# PDB2_1.net
KiCad netlist of a schematic drawn in EAGLE
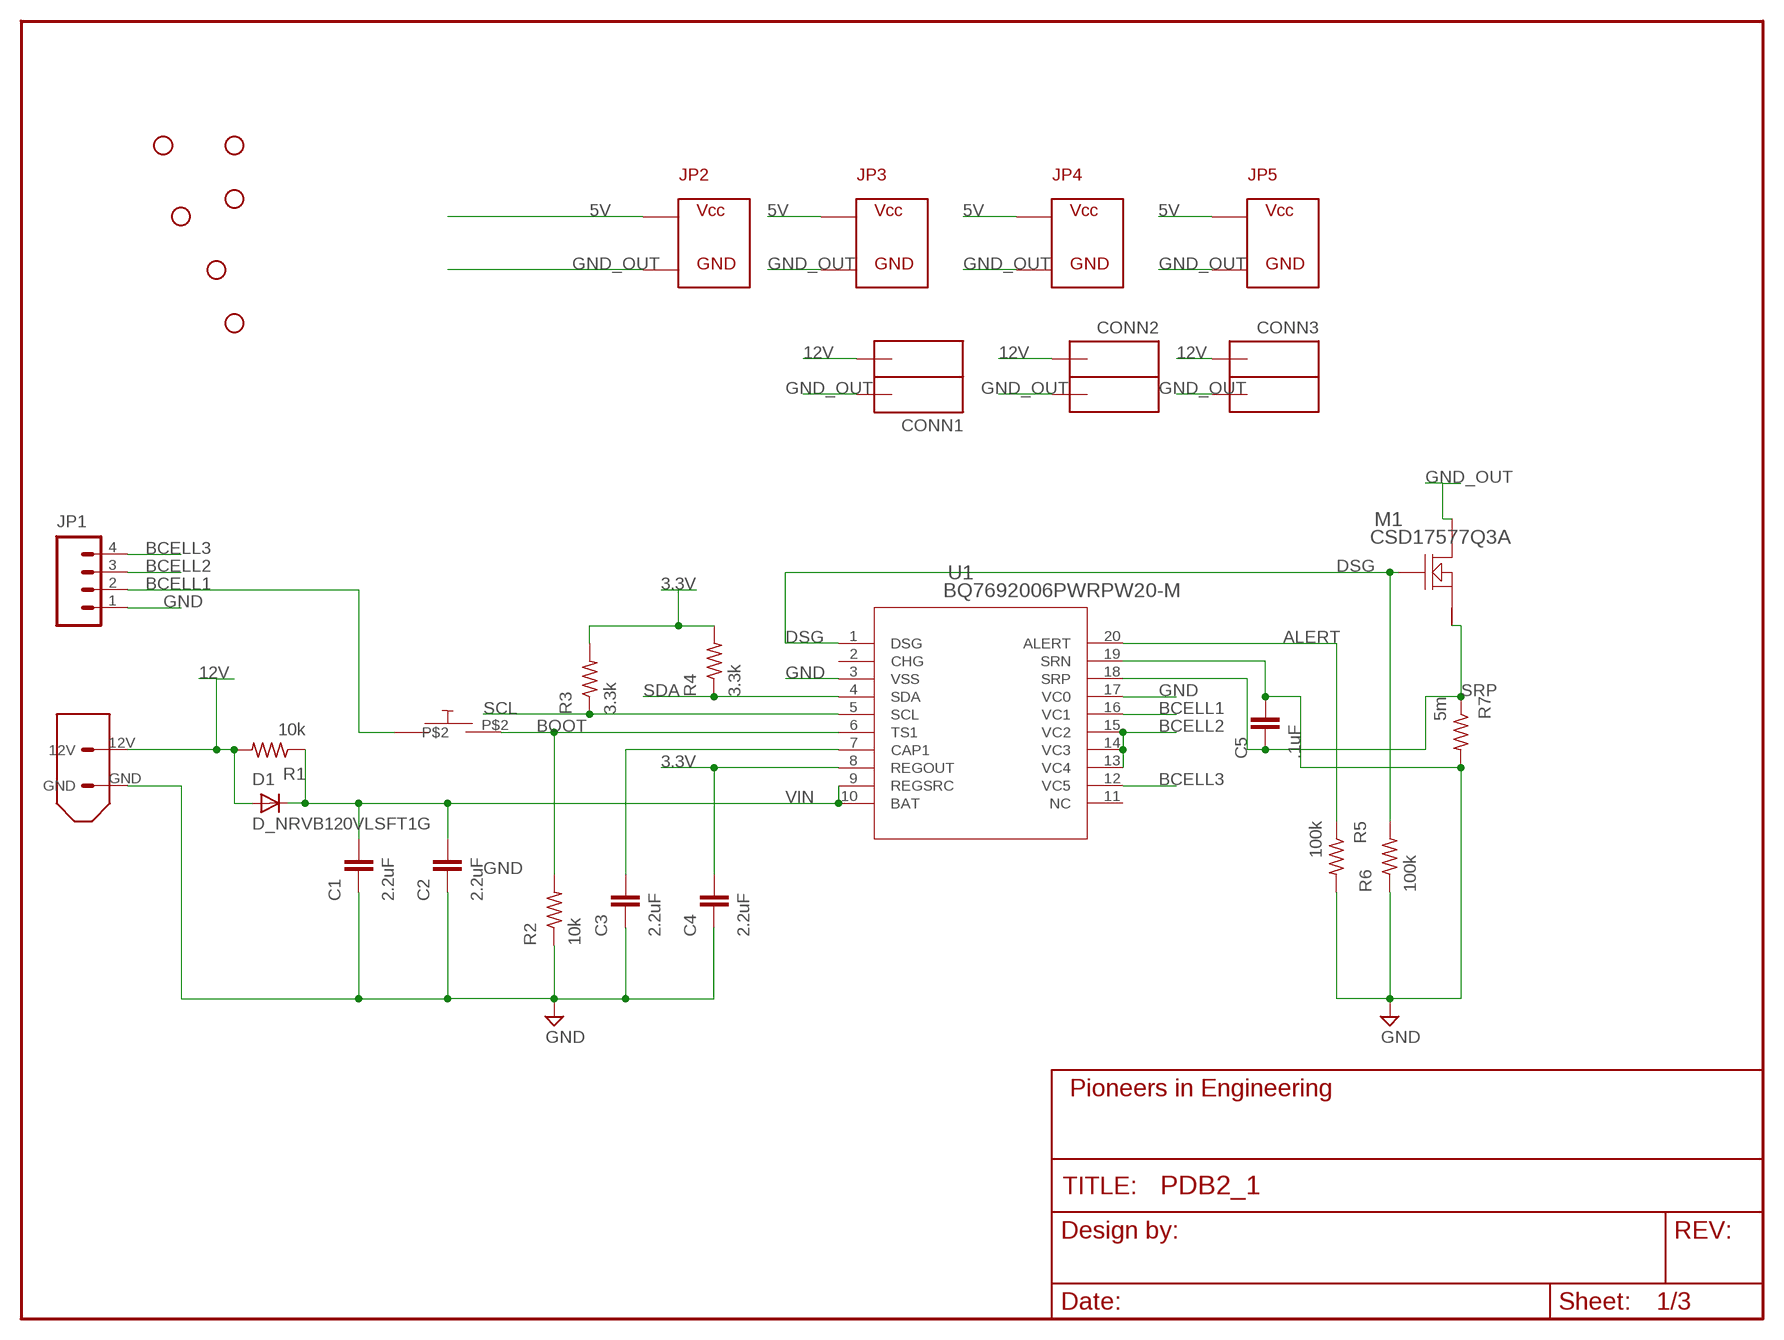
[diagram p0: schematic, sheet 1]
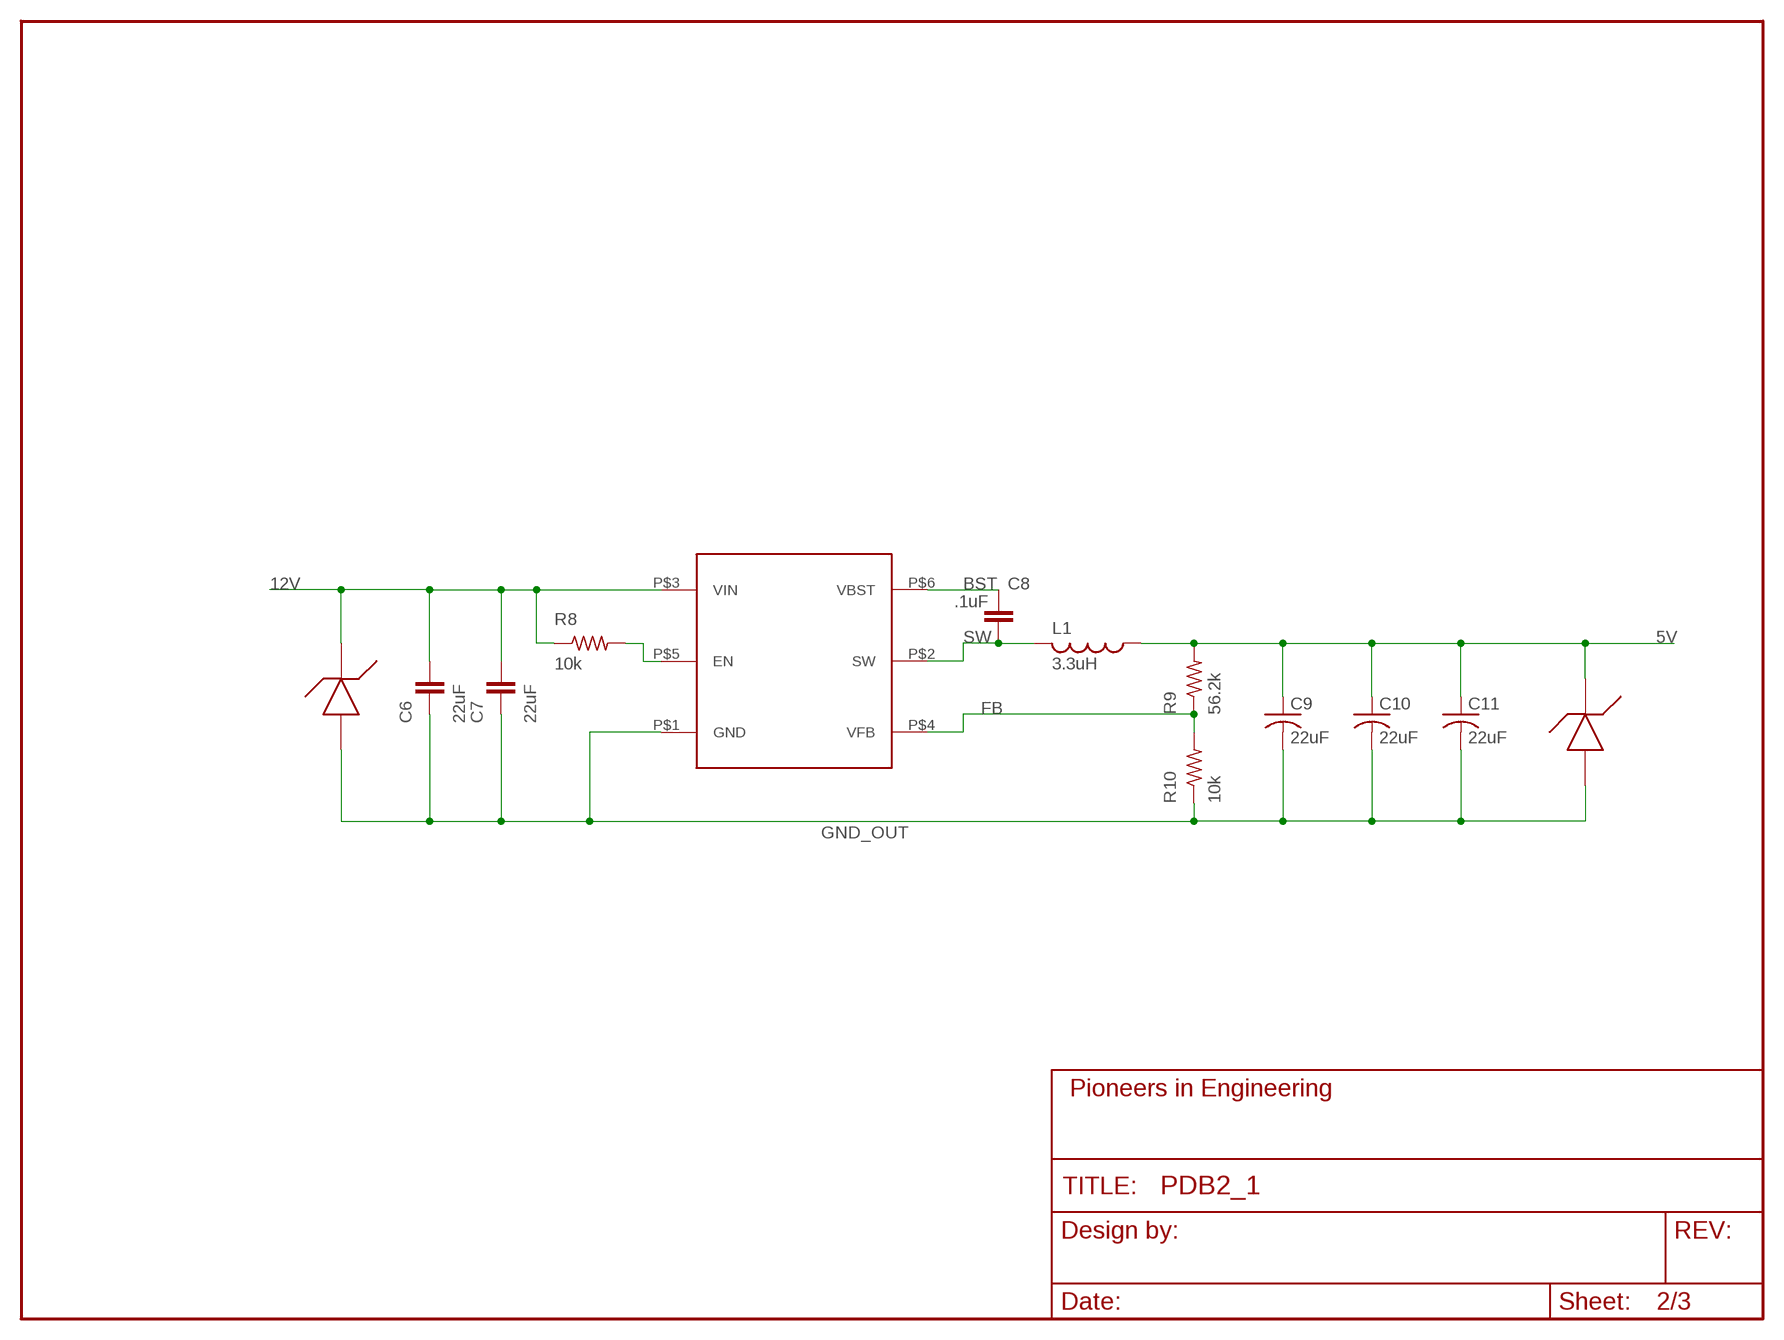
[diagram p1: schematic, sheet 2]
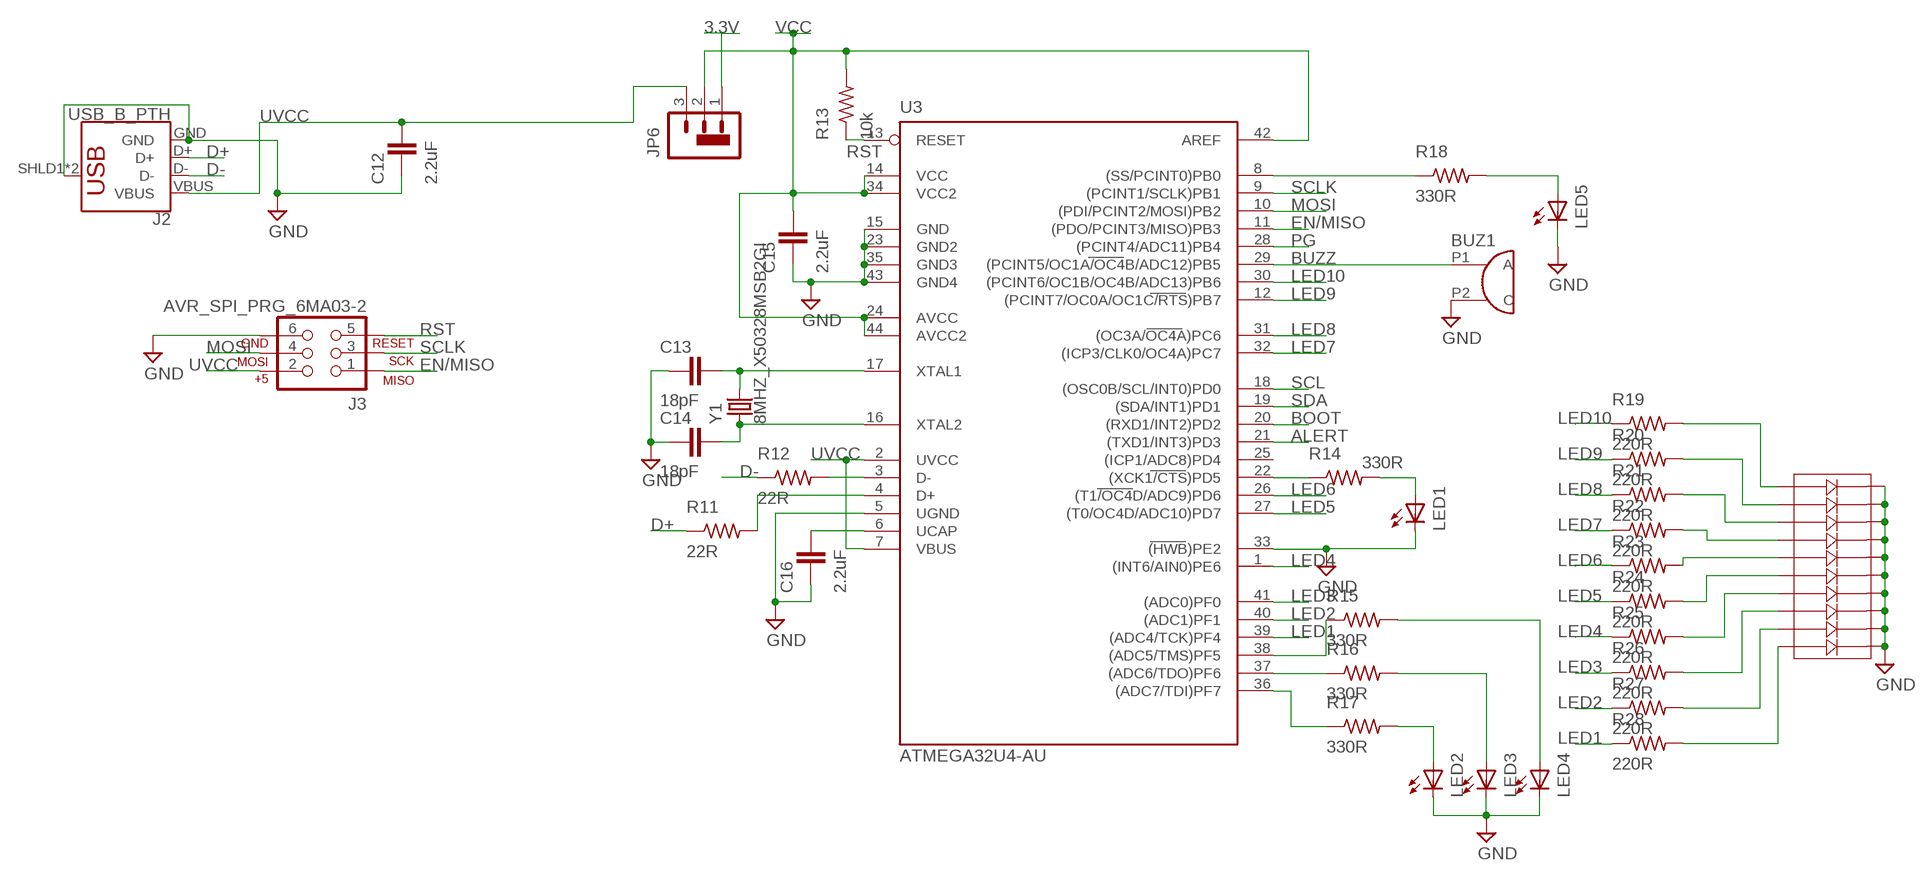
[diagram p2: schematic, sheet 3]

(export (version "E")
  (design (tool "Eeschema 10.0.6"))
  (components
    (comp (ref "BUZ1")
      (value "BUZZER3.3VBUZZER")
      (footprint "eagle-import:BUZZER_3.3V")
      (libsource (lib "eagle-import") (part "BUZZER3.3VBUZZER"))
    )
    (comp (ref "C12")
      (value "2.2uF")
      (footprint "eagle-import:0603-CAP")
      (libsource (lib "eagle-import") (part "CAP0603-CAP"))
    )
    (comp (ref "C13")
      (value "18pF")
      (footprint "eagle-import:0603-CAP")
      (libsource (lib "eagle-import") (part "CAP0603-CAP"))
    )
    (comp (ref "C14")
      (value "18pF")
      (footprint "eagle-import:0603-CAP")
      (libsource (lib "eagle-import") (part "CAP0603-CAP"))
    )
    (comp (ref "C15")
      (value "2.2uF")
      (footprint "eagle-import:0603-CAP")
      (libsource (lib "eagle-import") (part "CAP0603-CAP"))
    )
    (comp (ref "C16")
      (value "2.2uF")
      (footprint "eagle-import:0603-CAP")
      (libsource (lib "eagle-import") (part "CAP0603-CAP"))
    )
    (comp (ref "J2")
      (value "USB_B_PTH")
      (footprint "eagle-import:USB-B-PTH")
      (libsource (lib "eagle-import") (part "USB_B_PTH"))
    )
    (comp (ref "J3")
      (value "AVR_SPI_PRG_6MA03-2")
      (footprint "eagle-import:MA03-2")
      (libsource (lib "eagle-import") (part "AVR_SPI_PRG_6MA03-2"))
    )
    (comp (ref "JP6")
      (value "JMP-OPTION")
      (footprint "eagle-import:1X03-JMP-OPTION")
      (libsource (lib "eagle-import") (part "JMP-OPTION"))
    )
    (comp (ref "LED1")
      (value "LED0805")
      (footprint "eagle-import:LED-0805")
      (libsource (lib "eagle-import") (part "LED0805"))
    )
    (comp (ref "LED2")
      (value "LED0805")
      (footprint "eagle-import:LED-0805")
      (libsource (lib "eagle-import") (part "LED0805"))
    )
    (comp (ref "LED3")
      (value "LED0805")
      (footprint "eagle-import:LED-0805")
      (libsource (lib "eagle-import") (part "LED0805"))
    )
    (comp (ref "LED4")
      (value "LED0805")
      (footprint "eagle-import:LED-0805")
      (libsource (lib "eagle-import") (part "LED0805"))
    )
    (comp (ref "LED5")
      (value "LED0805")
      (footprint "eagle-import:LED-0805")
      (libsource (lib "eagle-import") (part "LED0805"))
    )
    (comp (ref "LED6")
      (value "BAR_SEGMENT_DISPLAY")
      (footprint "eagle-import:BAR_SEGMENT_DISPLAY")
      (libsource (lib "eagle-import") (part "BAR_SEGMENT_DISPLAY"))
    )
    (comp (ref "R11")
      (value "22R")
      (footprint "eagle-import:R0603")
      (fields (field (name "MANUFACTURER") "Rohm Semiconductor"))
      (libsource (lib "eagle-import") (part "R-US_R0603"))
    )
    (comp (ref "R12")
      (value "22R")
      (footprint "eagle-import:R0603")
      (fields (field (name "MANUFACTURER") "Rohm Semiconductor"))
      (libsource (lib "eagle-import") (part "R-US_R0603"))
    )
    (comp (ref "R13")
      (value "10k")
      (footprint "eagle-import:R0603")
      (fields (field (name "MANUFACTURER") "Rohm Semiconductor"))
      (libsource (lib "eagle-import") (part "R-US_R0603"))
    )
    (comp (ref "R14")
      (value "330R")
      (footprint "eagle-import:R0603")
      (fields (field (name "MANUFACTURER") "Rohm Semiconductor"))
      (libsource (lib "eagle-import") (part "R-US_R0603"))
    )
    (comp (ref "R15")
      (value "330R")
      (footprint "eagle-import:R0603")
      (fields (field (name "MANUFACTURER") "Rohm Semiconductor"))
      (libsource (lib "eagle-import") (part "R-US_R0603"))
    )
    (comp (ref "R16")
      (value "330R")
      (footprint "eagle-import:R0603")
      (fields (field (name "MANUFACTURER") "Rohm Semiconductor"))
      (libsource (lib "eagle-import") (part "R-US_R0603"))
    )
    (comp (ref "R17")
      (value "330R")
      (footprint "eagle-import:R0603")
      (fields (field (name "MANUFACTURER") "Rohm Semiconductor"))
      (libsource (lib "eagle-import") (part "R-US_R0603"))
    )
    (comp (ref "R18")
      (value "330R")
      (footprint "eagle-import:R0603")
      (fields (field (name "MANUFACTURER") "Rohm Semiconductor"))
      (libsource (lib "eagle-import") (part "R-US_R0603"))
    )
    (comp (ref "R19")
      (value "220R")
      (footprint "eagle-import:R0603")
      (fields (field (name "MANUFACTURER") "Rohm Semiconductor"))
      (libsource (lib "eagle-import") (part "R-US_R0603"))
    )
    (comp (ref "R20")
      (value "220R")
      (footprint "eagle-import:R0603")
      (fields (field (name "MANUFACTURER") "Rohm Semiconductor"))
      (libsource (lib "eagle-import") (part "R-US_R0603"))
    )
    (comp (ref "R21")
      (value "220R")
      (footprint "eagle-import:R0603")
      (fields (field (name "MANUFACTURER") "Rohm Semiconductor"))
      (libsource (lib "eagle-import") (part "R-US_R0603"))
    )
    (comp (ref "R22")
      (value "220R")
      (footprint "eagle-import:R0603")
      (fields (field (name "MANUFACTURER") "Rohm Semiconductor"))
      (libsource (lib "eagle-import") (part "R-US_R0603"))
    )
    (comp (ref "R23")
      (value "220R")
      (footprint "eagle-import:R0603")
      (fields (field (name "MANUFACTURER") "Rohm Semiconductor"))
      (libsource (lib "eagle-import") (part "R-US_R0603"))
    )
    (comp (ref "R24")
      (value "220R")
      (footprint "eagle-import:R0603")
      (fields (field (name "MANUFACTURER") "Rohm Semiconductor"))
      (libsource (lib "eagle-import") (part "R-US_R0603"))
    )
    (comp (ref "R25")
      (value "220R")
      (footprint "eagle-import:R0603")
      (fields (field (name "MANUFACTURER") "Rohm Semiconductor"))
      (libsource (lib "eagle-import") (part "R-US_R0603"))
    )
    (comp (ref "R26")
      (value "220R")
      (footprint "eagle-import:R0603")
      (fields (field (name "MANUFACTURER") "Rohm Semiconductor"))
      (libsource (lib "eagle-import") (part "R-US_R0603"))
    )
    (comp (ref "R27")
      (value "220R")
      (footprint "eagle-import:R0603")
      (fields (field (name "MANUFACTURER") "Rohm Semiconductor"))
      (libsource (lib "eagle-import") (part "R-US_R0603"))
    )
    (comp (ref "R28")
      (value "220R")
      (footprint "eagle-import:R0603")
      (fields (field (name "MANUFACTURER") "Rohm Semiconductor"))
      (libsource (lib "eagle-import") (part "R-US_R0603"))
    )
    (comp (ref "U3")
      (value "ATMEGA32U4-AU")
      (footprint "eagle-import:TQFP44")
      (libsource (lib "eagle-import") (part "ATMEGA32U4-AU"))
    )
    (comp (ref "Y1")
      (value "8MHZ_X50328MSB2GI")
      (footprint "eagle-import:SMD-5032_2P")
      (libsource (lib "eagle-import") (part "8MHZ_X50328MSB2GI"))
    )
    (comp (ref "C6")
      (value "22uF")
      (footprint "eagle-import:0805")
      (libsource (lib "eagle-import") (part "CAP0805"))
    )
    (comp (ref "C7")
      (value "22uF")
      (footprint "eagle-import:0805")
      (libsource (lib "eagle-import") (part "CAP0805"))
    )
    (comp (ref "C8")
      (value ".1uF")
      (footprint "eagle-import:0603-CAP")
      (libsource (lib "eagle-import") (part "CAP0603-CAP"))
    )
    (comp (ref "C9")
      (value "22uF")
      (footprint "eagle-import:C0805")
      (libsource (lib "eagle-import") (part "C-USC0805"))
    )
    (comp (ref "C10")
      (value "22uF")
      (footprint "eagle-import:C0805")
      (libsource (lib "eagle-import") (part "C-USC0805"))
    )
    (comp (ref "C11")
      (value "22uF")
      (footprint "eagle-import:C0805")
      (libsource (lib "eagle-import") (part "C-USC0805"))
    )
    (comp (ref "D2")
      (value "BZT52C2VXX_ZENER")
      (footprint "eagle-import:SOD-123")
      (libsource (lib "eagle-import") (part "BZT52C2VXX_ZENER"))
    )
    (comp (ref "D3")
      (value "BZT52C2VXX_ZENER")
      (footprint "eagle-import:SOD-123")
      (libsource (lib "eagle-import") (part "BZT52C2VXX_ZENER"))
    )
    (comp (ref "L1")
      (value "3.3uH")
      (footprint "eagle-import:MWSA0402S")
      (libsource (lib "eagle-import") (part "MWSA0420S_INDUCTORMW"))
    )
    (comp (ref "R8")
      (value "10k")
      (footprint "eagle-import:R0603")
      (fields (field (name "MANUFACTURER") "Rohm Semiconductor"))
      (libsource (lib "eagle-import") (part "R-US_R0603"))
    )
    (comp (ref "R9")
      (value "56.2k")
      (footprint "eagle-import:R0603")
      (fields (field (name "MANUFACTURER") "Rohm Semiconductor"))
      (libsource (lib "eagle-import") (part "R-US_R0603"))
    )
    (comp (ref "R10")
      (value "10k")
      (footprint "eagle-import:R0603")
      (fields (field (name "MANUFACTURER") "Rohm Semiconductor"))
      (libsource (lib "eagle-import") (part "R-US_R0603"))
    )
    (comp (ref "U2")
      (value "TPS563200")
      (footprint "eagle-import:SOT-23_6PIN_COPY")
      (libsource (lib "eagle-import") (part "TPS563200"))
    )
    (comp (ref "C1")
      (value "2.2uF")
      (footprint "eagle-import:0603-CAP")
      (libsource (lib "eagle-import") (part "CAP0603-CAP"))
    )
    (comp (ref "C2")
      (value "2.2uF")
      (footprint "eagle-import:0603-CAP")
      (libsource (lib "eagle-import") (part "CAP0603-CAP"))
    )
    (comp (ref "C3")
      (value "2.2uF")
      (footprint "eagle-import:0603-CAP")
      (libsource (lib "eagle-import") (part "CAP0603-CAP"))
    )
    (comp (ref "C4")
      (value "2.2uF")
      (footprint "eagle-import:0603-CAP")
      (libsource (lib "eagle-import") (part "CAP0603-CAP"))
    )
    (comp (ref "C5")
      (value ".1uF")
      (footprint "eagle-import:0603-CAP")
      (libsource (lib "eagle-import") (part "CAP0603-CAP"))
    )
    (comp (ref "CONN1")
      (value "ANDERSONVERTICAL")
      (footprint "eagle-import:ANDERSON_VERTICAL")
      (libsource (lib "eagle-import") (part "ANDERSONVERTICAL"))
    )
    (comp (ref "CONN2")
      (value "ANDERSONVERTICAL")
      (footprint "eagle-import:ANDERSON_VERTICAL")
      (libsource (lib "eagle-import") (part "ANDERSONVERTICAL"))
    )
    (comp (ref "CONN3")
      (value "ANDERSONVERTICAL")
      (footprint "eagle-import:ANDERSON_VERTICAL")
      (libsource (lib "eagle-import") (part "ANDERSONVERTICAL"))
    )
    (comp (ref "D1")
      (value "D_NRVB120VLSFT1G")
      (footprint "eagle-import:ON_SEMI_SOD-123F")
      (libsource (lib "eagle-import") (part "D_NRVB120VLSFT1G"))
    )
    (comp (ref "J1")
      (value "XT60CONNECTOR")
      (footprint "eagle-import:XT60CONNECTOR")
      (fields (field (name "PARTNUMBER") "PRT-10474 "))
      (libsource (lib "eagle-import") (part "XT60CONNECTOR"))
    )
    (comp (ref "JP1")
      (value "M041X04-MTA")
      (footprint "eagle-import:1X04-MTA")
      (libsource (lib "eagle-import") (part "M041X04-MTA"))
    )
    (comp (ref "JP2")
      (value "ATX")
      (footprint "eagle-import:ATX")
      (libsource (lib "eagle-import") (part "ATX"))
    )
    (comp (ref "JP3")
      (value "ATX")
      (footprint "eagle-import:ATX")
      (libsource (lib "eagle-import") (part "ATX"))
    )
    (comp (ref "JP4")
      (value "ATX")
      (footprint "eagle-import:ATX")
      (libsource (lib "eagle-import") (part "ATX"))
    )
    (comp (ref "JP5")
      (value "ATX")
      (footprint "eagle-import:ATX")
      (libsource (lib "eagle-import") (part "ATX"))
    )
    (comp (ref "M1")
      (value "CSD17577Q3A")
      (footprint "eagle-import:DNH0008A")
      (fields
        (field (name "MANUFACTURER_PART_NUMBER") "CSD17579Q3A")
        (field (name "MANUFACTURER_PART_NUMBER_1") "CSD17577Q3A")
      )
      (libsource (lib "eagle-import") (part "NMOS_CSD17579Q3A"))
    )
    (comp (ref "R1")
      (value "10k")
      (footprint "eagle-import:R0603")
      (fields (field (name "MANUFACTURER") "Rohm Semiconductor"))
      (libsource (lib "eagle-import") (part "R-US_R0603"))
    )
    (comp (ref "R2")
      (value "10k")
      (footprint "eagle-import:R0603")
      (fields (field (name "MANUFACTURER") "Rohm Semiconductor"))
      (libsource (lib "eagle-import") (part "R-US_R0603"))
    )
    (comp (ref "R3")
      (value "3.3k")
      (footprint "eagle-import:R0603")
      (fields (field (name "MANUFACTURER") "Rohm Semiconductor"))
      (libsource (lib "eagle-import") (part "R-US_R0603"))
    )
    (comp (ref "R4")
      (value "3.3k")
      (footprint "eagle-import:R0603")
      (fields (field (name "MANUFACTURER") "Rohm Semiconductor"))
      (libsource (lib "eagle-import") (part "R-US_R0603"))
    )
    (comp (ref "R5")
      (value "100k")
      (footprint "eagle-import:R0603")
      (fields (field (name "MANUFACTURER") "Rohm Semiconductor"))
      (libsource (lib "eagle-import") (part "R-US_R0603"))
    )
    (comp (ref "R6")
      (value "100k")
      (footprint "eagle-import:R0603")
      (fields (field (name "MANUFACTURER") "Rohm Semiconductor"))
      (libsource (lib "eagle-import") (part "R-US_R0603"))
    )
    (comp (ref "R7")
      (value "5m")
      (footprint "eagle-import:R2512")
      (libsource (lib "eagle-import") (part "R-US_R2512"))
    )
    (comp (ref "STANDOFF1")
      (value "STAND-OFFTIGHT")
      (footprint "eagle-import:STAND-OFF-TIGHT")
      (libsource (lib "eagle-import") (part "STAND-OFFTIGHT"))
    )
    (comp (ref "STANDOFF2")
      (value "STAND-OFFTIGHT")
      (footprint "eagle-import:STAND-OFF-TIGHT")
      (libsource (lib "eagle-import") (part "STAND-OFFTIGHT"))
    )
    (comp (ref "STANDOFF3")
      (value "STAND-OFFTIGHT")
      (footprint "eagle-import:STAND-OFF-TIGHT")
      (libsource (lib "eagle-import") (part "STAND-OFFTIGHT"))
    )
    (comp (ref "STANDOFF4")
      (value "STAND-OFFTIGHT")
      (footprint "eagle-import:STAND-OFF-TIGHT")
      (libsource (lib "eagle-import") (part "STAND-OFFTIGHT"))
    )
    (comp (ref "STANDOFF5")
      (value "STAND-OFFTIGHT")
      (footprint "eagle-import:STAND-OFF-TIGHT")
      (libsource (lib "eagle-import") (part "STAND-OFFTIGHT"))
    )
    (comp (ref "STANDOFF6")
      (value "STAND-OFFTIGHT")
      (footprint "eagle-import:STAND-OFF-TIGHT")
      (libsource (lib "eagle-import") (part "STAND-OFFTIGHT"))
    )
    (comp (ref "SW1")
      (value "PUSH_BUTTON")
      (footprint "eagle-import:BUTTON_K12A")
      (libsource (lib "eagle-import") (part "PUSH_BUTTON"))
    )
    (comp (ref "U1")
      (value "BQ7692006PWRPW20-M")
      (footprint "eagle-import:PW20-M")
      (fields (field (name "MANUFACTURER_PART_NUMBER") "BQ7692006PWR"))
      (libsource (lib "eagle-import") (part "BQ7692006PWRPW20-M"))
    )
  )
  (nets
    (net (code "1") (name "3.3V") (class "Default")
      (node (ref "C4") (pin "2") (pinfunction "2_2") (pintype "passive"))
      (node (ref "JP6") (pin "1") (pinfunction "1_1") (pintype "passive"))
      (node (ref "R3") (pin "2") (pinfunction "2_2") (pintype "passive"))
      (node (ref "R4") (pin "2") (pinfunction "2_2") (pintype "passive"))
      (node (ref "U1") (pin "8") (pinfunction "REGOUT_8") (pintype "power_in"))
    )
    (net (code "2") (name "5V") (class "Default")
      (node (ref "C10") (pin "1") (pinfunction "1_1") (pintype "passive"))
      (node (ref "C11") (pin "1") (pinfunction "1_1") (pintype "passive"))
      (node (ref "C9") (pin "1") (pinfunction "1_1") (pintype "passive"))
      (node (ref "D3") (pin "N") (pinfunction "N_N") (pintype "bidirectional"))
      (node (ref "JP2") (pin "P$1") (pinfunction "P$1_P$1") (pintype "power_in"))
      (node (ref "JP3") (pin "P$1") (pinfunction "P$1_P$1") (pintype "power_in"))
      (node (ref "JP4") (pin "P$1") (pinfunction "P$1_P$1") (pintype "power_in"))
      (node (ref "JP5") (pin "P$1") (pinfunction "P$1_P$1") (pintype "power_in"))
      (node (ref "L1") (pin "P$1") (pinfunction "1_P$1") (pintype "passive"))
      (node (ref "R9") (pin "2") (pinfunction "2_2") (pintype "passive"))
    )
    (net (code "3") (name "12V") (class "Default")
      (node (ref "C6") (pin "2") (pinfunction "2_2") (pintype "passive"))
      (node (ref "C7") (pin "2") (pinfunction "2_2") (pintype "passive"))
      (node (ref "CONN1") (pin "PIN1") (pinfunction "OUTB_PIN1") (pintype "bidirectional"))
      (node (ref "CONN2") (pin "PIN2") (pinfunction "OUTA_PIN2") (pintype "bidirectional"))
      (node (ref "CONN3") (pin "PIN2") (pinfunction "OUTA_PIN2") (pintype "bidirectional"))
      (node (ref "D1") (pin "P") (pinfunction "A_P") (pintype "passive"))
      (node (ref "D2") (pin "N") (pinfunction "N_N") (pintype "bidirectional"))
      (node (ref "J1") (pin "12V") (pinfunction "12V_12V") (pintype "bidirectional"))
      (node (ref "R1") (pin "2") (pinfunction "2_2") (pintype "passive"))
      (node (ref "R8") (pin "1") (pinfunction "1_1") (pintype "passive"))
      (node (ref "U2") (pin "P$3") (pinfunction "VIN_P$3") (pintype "bidirectional"))
    )
    (net (code "4") (name "ALERT") (class "Default")
      (node (ref "R5") (pin "1") (pinfunction "1_1") (pintype "passive"))
      (node (ref "U1") (pin "20") (pinfunction "ALERT_20") (pintype "bidirectional"))
      (node (ref "U3") (pin "21") (pinfunction "(TXD1/INT3)PD3_21") (pintype "bidirectional"))
    )
    (net (code "5") (name "BCELL1") (class "Default")
      (node (ref "JP1") (pin "2") (pinfunction "2_2") (pintype "passive"))
      (node (ref "SW1") (pin "P$1") (pinfunction "P$1_P$1") (pintype "bidirectional"))
      (node (ref "U1") (pin "16") (pinfunction "VC1_16") (pintype "input"))
    )
    (net (code "6") (name "BCELL2") (class "Default")
      (node (ref "JP1") (pin "3") (pinfunction "3_3") (pintype "passive"))
      (node (ref "U1") (pin "13") (pinfunction "VC4_13") (pintype "input"))
      (node (ref "U1") (pin "14") (pinfunction "VC3_14") (pintype "input"))
      (node (ref "U1") (pin "15") (pinfunction "VC2_15") (pintype "input"))
    )
    (net (code "7") (name "BCELL3") (class "Default")
      (node (ref "JP1") (pin "4") (pinfunction "4_4") (pintype "passive"))
      (node (ref "U1") (pin "12") (pinfunction "VC5_12") (pintype "input"))
    )
    (net (code "8") (name "BOOT") (class "Default")
      (node (ref "R2") (pin "2") (pinfunction "2_2") (pintype "passive"))
      (node (ref "SW1") (pin "P$2") (pinfunction "P$2_P$2") (pintype "bidirectional"))
      (node (ref "U1") (pin "6") (pinfunction "TS1_6") (pintype "input"))
      (node (ref "U3") (pin "20") (pinfunction "(RXD1/INT2)PD2_20") (pintype "bidirectional"))
    )
    (net (code "9") (name "BST") (class "Default")
      (node (ref "C8") (pin "1") (pinfunction "1_1") (pintype "passive"))
      (node (ref "U2") (pin "P$6") (pinfunction "VBST_P$6") (pintype "bidirectional"))
    )
    (net (code "10") (name "BUZZ") (class "Default")
      (node (ref "BUZ1") (pin "P1") (pinfunction "A_P1") (pintype "bidirectional"))
      (node (ref "U3") (pin "29") (pinfunction "(PCINT5/OC1A/OC4B/ADC12)PB5_29") (pintype "bidirectional"))
    )
    (net (code "11") (name "D+") (class "Default")
      (node (ref "J2") (pin "D+") (pinfunction "D+_D+") (pintype "bidirectional"))
      (node (ref "R11") (pin "1") (pinfunction "1_1") (pintype "passive"))
    )
    (net (code "12") (name "D-") (class "Default")
      (node (ref "J2") (pin "D-") (pinfunction "D-_D-") (pintype "bidirectional"))
      (node (ref "R12") (pin "1") (pinfunction "1_1") (pintype "passive"))
    )
    (net (code "13") (name "DSG") (class "Default")
      (node (ref "M1") (pin "4") (pinfunction "GATE_4") (pintype "passive"))
      (node (ref "R6") (pin "2") (pinfunction "2_2") (pintype "passive"))
      (node (ref "U1") (pin "1") (pinfunction "DSG_1") (pintype "output"))
    )
    (net (code "14") (name "EN{slash}MISO") (class "Default")
      (node (ref "J3") (pin "1") (pinfunction "1_1") (pintype "passive"))
      (node (ref "U3") (pin "11") (pinfunction "(PDO/PCINT3/MISO)PB3_11") (pintype "bidirectional"))
    )
    (net (code "15") (name "FB") (class "Default")
      (node (ref "R10") (pin "2") (pinfunction "2_2") (pintype "passive"))
      (node (ref "R9") (pin "1") (pinfunction "1_1") (pintype "passive"))
      (node (ref "U2") (pin "P$4") (pinfunction "VFB_P$4") (pintype "bidirectional"))
    )
    (net (code "16") (name "GND") (class "Default")
      (node (ref "BUZ1") (pin "P2") (pinfunction "C_P2") (pintype "bidirectional"))
      (node (ref "C1") (pin "1") (pinfunction "1_1") (pintype "passive"))
      (node (ref "C12") (pin "1") (pinfunction "1_1") (pintype "passive"))
      (node (ref "C13") (pin "1") (pinfunction "1_1") (pintype "passive"))
      (node (ref "C14") (pin "1") (pinfunction "1_1") (pintype "passive"))
      (node (ref "C15") (pin "1") (pinfunction "1_1") (pintype "passive"))
      (node (ref "C16") (pin "1") (pinfunction "1_1") (pintype "passive"))
      (node (ref "C2") (pin "1") (pinfunction "1_1") (pintype "passive"))
      (node (ref "C3") (pin "1") (pinfunction "1_1") (pintype "passive"))
      (node (ref "C4") (pin "1") (pinfunction "1_1") (pintype "passive"))
      (node (ref "C5") (pin "2") (pinfunction "2_2") (pintype "passive"))
      (node (ref "J1") (pin "GND") (pinfunction "GND_GND") (pintype "bidirectional"))
      (node (ref "J2") (pin "GND") (pinfunction "GND_GND") (pintype "power_in"))
      (node (ref "J2") (pin "SHLD1") (pinfunction "SHIELD_SHLD1") (pintype "bidirectional"))
      (node (ref "J2") (pin "SHLD2") (pinfunction "SHIELD_SHLD2") (pintype "bidirectional"))
      (node (ref "J3") (pin "6") (pinfunction "6_6") (pintype "passive"))
      (node (ref "JP1") (pin "1") (pinfunction "1_1") (pintype "passive"))
      (node (ref "LED1") (pin "C") (pinfunction "C_C") (pintype "passive"))
      (node (ref "LED2") (pin "C") (pinfunction "C_C") (pintype "passive"))
      (node (ref "LED3") (pin "C") (pinfunction "C_C") (pintype "passive"))
      (node (ref "LED4") (pin "C") (pinfunction "C_C") (pintype "passive"))
      (node (ref "LED5") (pin "C") (pinfunction "C_C") (pintype "passive"))
      (node (ref "LED6") (pin "BAR_DISPLAY10") (pinfunction "P11_BAR_DISPLAY10") (pintype "bidirectional"))
      (node (ref "LED6") (pin "BAR_DISPLAY11") (pinfunction "P12_BAR_DISPLAY11") (pintype "bidirectional"))
      (node (ref "LED6") (pin "BAR_DISPLAY12") (pinfunction "P13_BAR_DISPLAY12") (pintype "bidirectional"))
      (node (ref "LED6") (pin "BAR_DISPLAY13") (pinfunction "P14_BAR_DISPLAY13") (pintype "bidirectional"))
      (node (ref "LED6") (pin "BAR_DISPLAY14") (pinfunction "P15_BAR_DISPLAY14") (pintype "bidirectional"))
      (node (ref "LED6") (pin "BAR_DISPLAY15") (pinfunction "P16_BAR_DISPLAY15") (pintype "bidirectional"))
      (node (ref "LED6") (pin "BAR_DISPLAY16") (pinfunction "P17_BAR_DISPLAY16") (pintype "bidirectional"))
      (node (ref "LED6") (pin "BAR_DISPLAY17") (pinfunction "P18_BAR_DISPLAY17") (pintype "bidirectional"))
      (node (ref "LED6") (pin "BAR_DISPLAY18") (pinfunction "P19_BAR_DISPLAY18") (pintype "bidirectional"))
      (node (ref "LED6") (pin "BAR_DISPLAY19") (pinfunction "P20_BAR_DISPLAY19") (pintype "bidirectional"))
      (node (ref "R2") (pin "1") (pinfunction "1_1") (pintype "passive"))
      (node (ref "R5") (pin "2") (pinfunction "2_2") (pintype "passive"))
      (node (ref "R6") (pin "1") (pinfunction "1_1") (pintype "passive"))
      (node (ref "R7") (pin "2") (pinfunction "2_2") (pintype "passive"))
      (node (ref "U1") (pin "17") (pinfunction "VC0_17") (pintype "input"))
      (node (ref "U1") (pin "19") (pinfunction "SRN_19") (pintype "input"))
      (node (ref "U1") (pin "3") (pinfunction "VSS_3") (pintype "power_in"))
      (node (ref "U3") (pin "15") (pinfunction "GND_15") (pintype "bidirectional"))
      (node (ref "U3") (pin "23") (pinfunction "GND2_23") (pintype "bidirectional"))
      (node (ref "U3") (pin "33") (pinfunction "(HWB)PE2_33") (pintype "bidirectional"))
      (node (ref "U3") (pin "35") (pinfunction "GND3_35") (pintype "bidirectional"))
      (node (ref "U3") (pin "43") (pinfunction "GND4_43") (pintype "bidirectional"))
      (node (ref "U3") (pin "5") (pinfunction "UGND_5") (pintype "bidirectional"))
    )
    (net (code "17") (name "GND_OUT") (class "Default")
      (node (ref "C10") (pin "2") (pinfunction "2_2") (pintype "passive"))
      (node (ref "C11") (pin "2") (pinfunction "2_2") (pintype "passive"))
      (node (ref "C6") (pin "1") (pinfunction "1_1") (pintype "passive"))
      (node (ref "C7") (pin "1") (pinfunction "1_1") (pintype "passive"))
      (node (ref "C9") (pin "2") (pinfunction "2_2") (pintype "passive"))
      (node (ref "CONN1") (pin "PIN2") (pinfunction "OUTA_PIN2") (pintype "bidirectional"))
      (node (ref "CONN2") (pin "PIN1") (pinfunction "OUTB_PIN1") (pintype "bidirectional"))
      (node (ref "CONN3") (pin "PIN1") (pinfunction "OUTB_PIN1") (pintype "bidirectional"))
      (node (ref "D2") (pin "P") (pinfunction "P_P") (pintype "bidirectional"))
      (node (ref "D3") (pin "P") (pinfunction "P_P") (pintype "bidirectional"))
      (node (ref "JP2") (pin "P$2") (pinfunction "P$2_P$2") (pintype "power_in"))
      (node (ref "JP3") (pin "P$2") (pinfunction "P$2_P$2") (pintype "power_in"))
      (node (ref "JP4") (pin "P$2") (pinfunction "P$2_P$2") (pintype "power_in"))
      (node (ref "JP5") (pin "P$2") (pinfunction "P$2_P$2") (pintype "power_in"))
      (node (ref "M1") (pin "5") (pinfunction "DRAIN_2_5") (pintype "passive"))
      (node (ref "M1") (pin "6") (pinfunction "DRAIN_2_6") (pintype "passive"))
      (node (ref "M1") (pin "7") (pinfunction "DRAIN_2_7") (pintype "passive"))
      (node (ref "M1") (pin "8") (pinfunction "DRAIN_2_8") (pintype "passive"))
      (node (ref "M1") (pin "9") (pinfunction "DRAIN_2_9") (pintype "passive"))
      (node (ref "R10") (pin "1") (pinfunction "1_1") (pintype "passive"))
      (node (ref "U2") (pin "P$1") (pinfunction "GND_P$1") (pintype "bidirectional"))
    )
    (net (code "18") (name "LED1") (class "Default")
      (node (ref "R28") (pin "1") (pinfunction "1_1") (pintype "passive"))
      (node (ref "U3") (pin "39") (pinfunction "(ADC4/TCK)PF4_39") (pintype "bidirectional"))
    )
    (net (code "19") (name "LED2") (class "Default")
      (node (ref "R27") (pin "1") (pinfunction "1_1") (pintype "passive"))
      (node (ref "U3") (pin "40") (pinfunction "(ADC1)PF1_40") (pintype "bidirectional"))
    )
    (net (code "20") (name "LED3") (class "Default")
      (node (ref "R26") (pin "1") (pinfunction "1_1") (pintype "passive"))
      (node (ref "U3") (pin "41") (pinfunction "(ADC0)PF0_41") (pintype "bidirectional"))
    )
    (net (code "21") (name "LED4") (class "Default")
      (node (ref "R25") (pin "1") (pinfunction "1_1") (pintype "passive"))
      (node (ref "U3") (pin "1") (pinfunction "(INT6/AIN0)PE6_1") (pintype "bidirectional"))
    )
    (net (code "22") (name "LED5") (class "Default")
      (node (ref "R24") (pin "1") (pinfunction "1_1") (pintype "passive"))
      (node (ref "U3") (pin "27") (pinfunction "(T0/OC4D/ADC10)PD7_27") (pintype "bidirectional"))
    )
    (net (code "23") (name "LED6") (class "Default")
      (node (ref "R23") (pin "1") (pinfunction "1_1") (pintype "passive"))
      (node (ref "U3") (pin "26") (pinfunction "(T1/OC4D/ADC9)PD6_26") (pintype "bidirectional"))
    )
    (net (code "24") (name "LED7") (class "Default")
      (node (ref "R22") (pin "1") (pinfunction "1_1") (pintype "passive"))
      (node (ref "U3") (pin "32") (pinfunction "(ICP3/CLK0/OC4A)PC7_32") (pintype "bidirectional"))
    )
    (net (code "25") (name "LED8") (class "Default")
      (node (ref "R21") (pin "1") (pinfunction "1_1") (pintype "passive"))
      (node (ref "U3") (pin "31") (pinfunction "(OC3A/OC4A)PC6_31") (pintype "bidirectional"))
    )
    (net (code "26") (name "LED9") (class "Default")
      (node (ref "R20") (pin "1") (pinfunction "1_1") (pintype "passive"))
      (node (ref "U3") (pin "12") (pinfunction "(PCINT7/OC0A/OC1C/RTS)PB7_12") (pintype "bidirectional"))
    )
    (net (code "27") (name "LED10") (class "Default")
      (node (ref "R19") (pin "1") (pinfunction "1_1") (pintype "passive"))
      (node (ref "U3") (pin "30") (pinfunction "(PCINT6/OC1B/OC4B/ADC13)PB6_30") (pintype "bidirectional"))
    )
    (net (code "28") (name "MOSI") (class "Default")
      (node (ref "J3") (pin "4") (pinfunction "4_4") (pintype "passive"))
      (node (ref "U3") (pin "10") (pinfunction "(PDI/PCINT2/MOSI)PB2_10") (pintype "bidirectional"))
    )
    (net (code "29") (name "Net-(LED1-PadA)") (class "Default")
      (node (ref "LED1") (pin "A") (pinfunction "A_A") (pintype "passive"))
      (node (ref "R14") (pin "2") (pinfunction "2_2") (pintype "passive"))
    )
    (net (code "30") (name "Net-(LED2-PadA)") (class "Default")
      (node (ref "LED2") (pin "A") (pinfunction "A_A") (pintype "passive"))
      (node (ref "R17") (pin "2") (pinfunction "2_2") (pintype "passive"))
    )
    (net (code "31") (name "Net-(LED3-PadA)") (class "Default")
      (node (ref "LED3") (pin "A") (pinfunction "A_A") (pintype "passive"))
      (node (ref "R16") (pin "2") (pinfunction "2_2") (pintype "passive"))
    )
    (net (code "32") (name "Net-(LED4-PadA)") (class "Default")
      (node (ref "LED4") (pin "A") (pinfunction "A_A") (pintype "passive"))
      (node (ref "R15") (pin "2") (pinfunction "2_2") (pintype "passive"))
    )
    (net (code "33") (name "Net-(LED5-PadA)") (class "Default")
      (node (ref "LED5") (pin "A") (pinfunction "A_A") (pintype "passive"))
      (node (ref "R18") (pin "2") (pinfunction "2_2") (pintype "passive"))
    )
    (net (code "34") (name "Net-(LED6-P1)") (class "Default")
      (node (ref "LED6") (pin "BAR_DISPLAY0") (pinfunction "P1_BAR_DISPLAY0") (pintype "bidirectional"))
      (node (ref "R19") (pin "2") (pinfunction "2_2") (pintype "passive"))
    )
    (net (code "35") (name "Net-(LED6-P2)") (class "Default")
      (node (ref "LED6") (pin "BAR_DISPLAY1") (pinfunction "P2_BAR_DISPLAY1") (pintype "bidirectional"))
      (node (ref "R20") (pin "2") (pinfunction "2_2") (pintype "passive"))
    )
    (net (code "36") (name "Net-(LED6-P3)") (class "Default")
      (node (ref "LED6") (pin "BAR_DISPLAY2") (pinfunction "P3_BAR_DISPLAY2") (pintype "bidirectional"))
      (node (ref "R21") (pin "2") (pinfunction "2_2") (pintype "passive"))
    )
    (net (code "37") (name "Net-(LED6-P4)") (class "Default")
      (node (ref "LED6") (pin "BAR_DISPLAY3") (pinfunction "P4_BAR_DISPLAY3") (pintype "bidirectional"))
      (node (ref "R22") (pin "2") (pinfunction "2_2") (pintype "passive"))
    )
    (net (code "38") (name "Net-(LED6-P5)") (class "Default")
      (node (ref "LED6") (pin "BAR_DISPLAY4") (pinfunction "P5_BAR_DISPLAY4") (pintype "bidirectional"))
      (node (ref "R23") (pin "2") (pinfunction "2_2") (pintype "passive"))
    )
    (net (code "39") (name "Net-(LED6-P6)") (class "Default")
      (node (ref "LED6") (pin "BAR_DISPLAY5") (pinfunction "P6_BAR_DISPLAY5") (pintype "bidirectional"))
      (node (ref "R24") (pin "2") (pinfunction "2_2") (pintype "passive"))
    )
    (net (code "40") (name "Net-(LED6-P7)") (class "Default")
      (node (ref "LED6") (pin "BAR_DISPLAY6") (pinfunction "P7_BAR_DISPLAY6") (pintype "bidirectional"))
      (node (ref "R25") (pin "2") (pinfunction "2_2") (pintype "passive"))
    )
    (net (code "41") (name "Net-(LED6-P8)") (class "Default")
      (node (ref "LED6") (pin "BAR_DISPLAY7") (pinfunction "P8_BAR_DISPLAY7") (pintype "bidirectional"))
      (node (ref "R26") (pin "2") (pinfunction "2_2") (pintype "passive"))
    )
    (net (code "42") (name "Net-(LED6-P9)") (class "Default")
      (node (ref "LED6") (pin "BAR_DISPLAY8") (pinfunction "P9_BAR_DISPLAY8") (pintype "bidirectional"))
      (node (ref "R27") (pin "2") (pinfunction "2_2") (pintype "passive"))
    )
    (net (code "43") (name "Net-(LED6-P10)") (class "Default")
      (node (ref "LED6") (pin "BAR_DISPLAY9") (pinfunction "P10_BAR_DISPLAY9") (pintype "bidirectional"))
      (node (ref "R28") (pin "2") (pinfunction "2_2") (pintype "passive"))
    )
    (net (code "44") (name "Net-(U1-CAP1)") (class "Default")
      (node (ref "C3") (pin "2") (pinfunction "2_2") (pintype "passive"))
      (node (ref "U1") (pin "7") (pinfunction "CAP1_7") (pintype "output"))
    )
    (net (code "45") (name "Net-(U2-EN)") (class "Default")
      (node (ref "R8") (pin "2") (pinfunction "2_2") (pintype "passive"))
      (node (ref "U2") (pin "P$5") (pinfunction "EN_P$5") (pintype "bidirectional"))
    )
    (net (code "46") (name "Net-(U3-(ADC5{slash}TMS)PF5)") (class "Default")
      (node (ref "R15") (pin "1") (pinfunction "1_1") (pintype "passive"))
      (node (ref "U3") (pin "38") (pinfunction "(ADC5/TMS)PF5_38") (pintype "bidirectional"))
    )
    (net (code "47") (name "Net-(U3-(ADC6{slash}TDO)PF6)") (class "Default")
      (node (ref "R16") (pin "1") (pinfunction "1_1") (pintype "passive"))
      (node (ref "U3") (pin "37") (pinfunction "(ADC6/TDO)PF6_37") (pintype "bidirectional"))
    )
    (net (code "48") (name "Net-(U3-(ADC7{slash}TDI)PF7)") (class "Default")
      (node (ref "R17") (pin "1") (pinfunction "1_1") (pintype "passive"))
      (node (ref "U3") (pin "36") (pinfunction "(ADC7/TDI)PF7_36") (pintype "bidirectional"))
    )
    (net (code "49") (name "Net-(U3-(SS{slash}PCINT0)PB0)") (class "Default")
      (node (ref "R18") (pin "1") (pinfunction "1_1") (pintype "passive"))
      (node (ref "U3") (pin "8") (pinfunction "(SS/PCINT0)PB0_8") (pintype "bidirectional"))
    )
    (net (code "50") (name "Net-(U3-(XCK1{slash}CTS)PD5)") (class "Default")
      (node (ref "R14") (pin "1") (pinfunction "1_1") (pintype "passive"))
      (node (ref "U3") (pin "22") (pinfunction "(XCK1/CTS)PD5_22") (pintype "bidirectional"))
    )
    (net (code "51") (name "Net-(U3-D+)") (class "Default")
      (node (ref "R11") (pin "2") (pinfunction "2_2") (pintype "passive"))
      (node (ref "U3") (pin "4") (pinfunction "D+_4") (pintype "bidirectional"))
    )
    (net (code "52") (name "Net-(U3-D-)") (class "Default")
      (node (ref "R12") (pin "2") (pinfunction "2_2") (pintype "passive"))
      (node (ref "U3") (pin "3") (pinfunction "D-_3") (pintype "bidirectional"))
    )
    (net (code "53") (name "Net-(U3-UCAP)") (class "Default")
      (node (ref "C16") (pin "2") (pinfunction "2_2") (pintype "passive"))
      (node (ref "U3") (pin "6") (pinfunction "UCAP_6") (pintype "bidirectional"))
    )
    (net (code "54") (name "Net-(U3-XTAL1)") (class "Default")
      (node (ref "C13") (pin "2") (pinfunction "2_2") (pintype "passive"))
      (node (ref "U3") (pin "17") (pinfunction "XTAL1_17") (pintype "bidirectional"))
      (node (ref "Y1") (pin "P$2") (pinfunction "2_P$2") (pintype "passive"))
    )
    (net (code "55") (name "Net-(U3-XTAL2)") (class "Default")
      (node (ref "C14") (pin "2") (pinfunction "2_2") (pintype "passive"))
      (node (ref "U3") (pin "16") (pinfunction "XTAL2_16") (pintype "bidirectional"))
      (node (ref "Y1") (pin "P$1") (pinfunction "1_P$1") (pintype "passive"))
    )
    (net (code "56") (name "PG") (class "Default")
      (node (ref "U3") (pin "28") (pinfunction "(PCINT4/ADC11)PB4_28") (pintype "bidirectional"))
    )
    (net (code "57") (name "RST") (class "Default")
      (node (ref "J3") (pin "5") (pinfunction "5_5") (pintype "passive"))
      (node (ref "R13") (pin "1") (pinfunction "1_1") (pintype "passive"))
      (node (ref "U3") (pin "13") (pinfunction "RESET_13") (pintype "bidirectional"))
    )
    (net (code "58") (name "SCL") (class "Default")
      (node (ref "R3") (pin "1") (pinfunction "1_1") (pintype "passive"))
      (node (ref "U1") (pin "5") (pinfunction "SCL_5") (pintype "input"))
      (node (ref "U3") (pin "18") (pinfunction "(OSC0B/SCL/INT0)PD0_18") (pintype "bidirectional"))
    )
    (net (code "59") (name "SCLK") (class "Default")
      (node (ref "J3") (pin "3") (pinfunction "3_3") (pintype "passive"))
      (node (ref "U3") (pin "9") (pinfunction "(PCINT1/SCLK)PB1_9") (pintype "bidirectional"))
    )
    (net (code "60") (name "SDA") (class "Default")
      (node (ref "R4") (pin "1") (pinfunction "1_1") (pintype "passive"))
      (node (ref "U1") (pin "4") (pinfunction "SDA_4") (pintype "bidirectional"))
      (node (ref "U3") (pin "19") (pinfunction "(SDA/INT1)PD1_19") (pintype "bidirectional"))
    )
    (net (code "61") (name "SRP") (class "Default")
      (node (ref "C5") (pin "1") (pinfunction "1_1") (pintype "passive"))
      (node (ref "M1") (pin "1") (pinfunction "SOURCE_2_1") (pintype "passive"))
      (node (ref "M1") (pin "2") (pinfunction "SOURCE_2_2") (pintype "passive"))
      (node (ref "M1") (pin "3") (pinfunction "SOURCE_2_3") (pintype "passive"))
      (node (ref "R7") (pin "1") (pinfunction "1_1") (pintype "passive"))
      (node (ref "U1") (pin "18") (pinfunction "SRP_18") (pintype "input"))
    )
    (net (code "62") (name "SW") (class "Default")
      (node (ref "C8") (pin "2") (pinfunction "2_2") (pintype "passive"))
      (node (ref "L1") (pin "P$2") (pinfunction "2_P$2") (pintype "passive"))
      (node (ref "U2") (pin "P$2") (pinfunction "SW_P$2") (pintype "bidirectional"))
    )
    (net (code "63") (name "UVCC") (class "Default")
      (node (ref "C12") (pin "2") (pinfunction "2_2") (pintype "passive"))
      (node (ref "J2") (pin "VBUS") (pinfunction "VBUS_VBUS") (pintype "power_in"))
      (node (ref "J3") (pin "2") (pinfunction "2_2") (pintype "passive"))
      (node (ref "JP6") (pin "3") (pinfunction "3_3") (pintype "passive"))
      (node (ref "U3") (pin "2") (pinfunction "UVCC_2") (pintype "bidirectional"))
      (node (ref "U3") (pin "7") (pinfunction "VBUS_7") (pintype "bidirectional"))
    )
    (net (code "64") (name "VCC") (class "Default")
      (node (ref "C15") (pin "2") (pinfunction "2_2") (pintype "passive"))
      (node (ref "JP6") (pin "2") (pinfunction "COMMON_2") (pintype "passive"))
      (node (ref "R13") (pin "2") (pinfunction "2_2") (pintype "passive"))
      (node (ref "U3") (pin "14") (pinfunction "VCC_14") (pintype "bidirectional"))
      (node (ref "U3") (pin "24") (pinfunction "AVCC_24") (pintype "bidirectional"))
      (node (ref "U3") (pin "34") (pinfunction "VCC2_34") (pintype "bidirectional"))
      (node (ref "U3") (pin "42") (pinfunction "AREF_42") (pintype "bidirectional"))
      (node (ref "U3") (pin "44") (pinfunction "AVCC2_44") (pintype "bidirectional"))
    )
    (net (code "65") (name "VIN") (class "Default")
      (node (ref "C1") (pin "2") (pinfunction "2_2") (pintype "passive"))
      (node (ref "C2") (pin "2") (pinfunction "2_2") (pintype "passive"))
      (node (ref "D1") (pin "N") (pinfunction "C_N") (pintype "passive"))
      (node (ref "R1") (pin "1") (pinfunction "1_1") (pintype "passive"))
      (node (ref "U1") (pin "10") (pinfunction "BAT_10") (pintype "power_in"))
      (node (ref "U1") (pin "9") (pinfunction "REGSRC_9") (pintype "input"))
    )
    (net (code "66") (name "unconnected-(U1-CHG-Pad2)") (class "Default")
      (node (ref "U1") (pin "2") (pinfunction "CHG_2") (pintype "output"))
    )
    (net (code "67") (name "unconnected-(U1-NC-Pad11)") (class "Default")
      (node (ref "U1") (pin "11") (pinfunction "NC_11") (pintype "no_connect"))
    )
    (net (code "68") (name "unconnected-(U3-(ICP1{slash}ADC8)PD4-Pad25)") (class "Default")
      (node (ref "U3") (pin "25") (pinfunction "(ICP1/ADC8)PD4_25") (pintype "bidirectional"))
    )
  )
)
